# Oasis_embedded_system_2020-12-29_17-35-1.net
KiCad netlist of a schematic drawn in EasyEDA
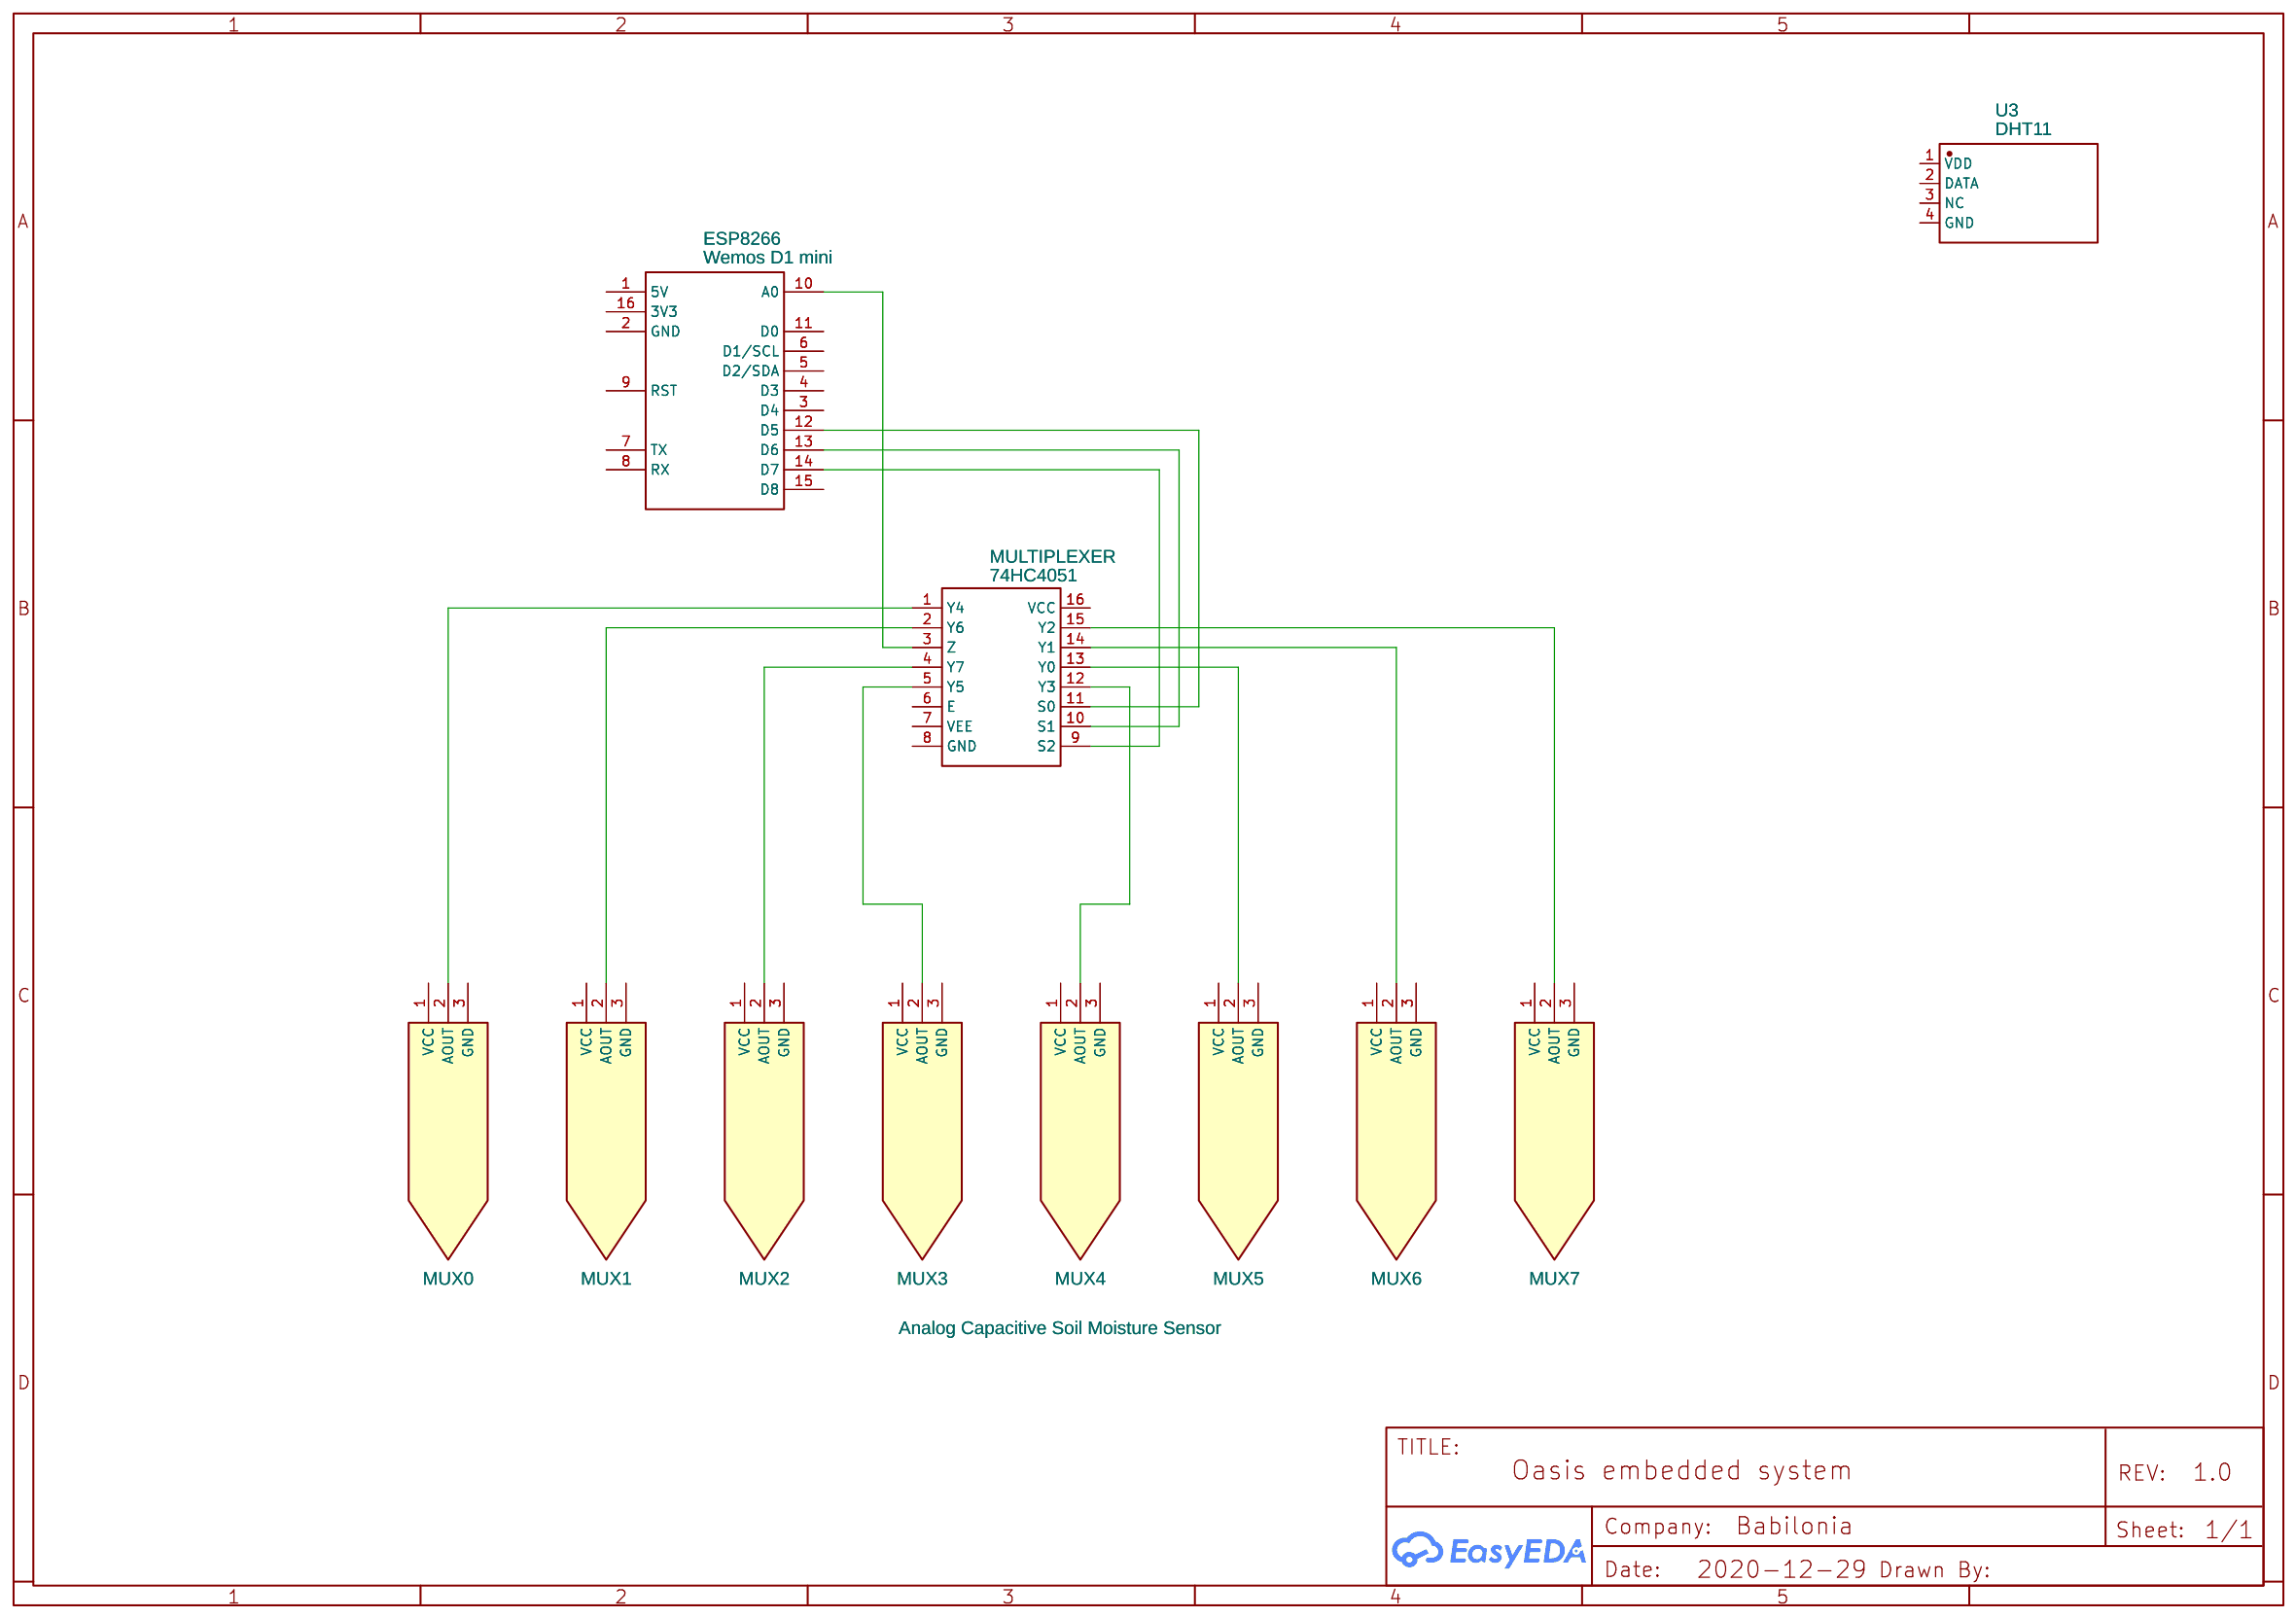
[diagram p0: schematic sheet]

(export (version "E")
  (design (tool "Eeschema 10.0.6"))
  (components
    (comp (ref "ESP8266") (value "Wemos D1 mini") (libsource (lib "") (part "Wemos D1 mini")))
    (comp (ref "MULTIPLEXER") (value "74HC4051") (libsource (lib "") (part "74HC4051")))
    (comp (ref "MUX0")
      (value "Analog Capacitive Soil Moisture Sensor")
      (fields (field (name "BOM_Manufacturer Part") "New SchematicLib"))
      (libsource (lib "") (part "Analog Capacitive Soil Moisture Sensor"))
    )
    (comp (ref "MUX1")
      (value "Analog Capacitive Soil Moisture Sensor")
      (fields (field (name "BOM_Manufacturer Part") "New SchematicLib"))
      (libsource (lib "") (part "Analog Capacitive Soil Moisture Sensor"))
    )
    (comp (ref "MUX2")
      (value "Analog Capacitive Soil Moisture Sensor")
      (fields (field (name "BOM_Manufacturer Part") "New SchematicLib"))
      (libsource (lib "") (part "Analog Capacitive Soil Moisture Sensor"))
    )
    (comp (ref "MUX3")
      (value "Analog Capacitive Soil Moisture Sensor")
      (fields (field (name "BOM_Manufacturer Part") "New SchematicLib"))
      (libsource (lib "") (part "Analog Capacitive Soil Moisture Sensor"))
    )
    (comp (ref "MUX4")
      (value "Analog Capacitive Soil Moisture Sensor")
      (fields (field (name "BOM_Manufacturer Part") "New SchematicLib"))
      (libsource (lib "") (part "Analog Capacitive Soil Moisture Sensor"))
    )
    (comp (ref "MUX5")
      (value "Analog Capacitive Soil Moisture Sensor")
      (fields (field (name "BOM_Manufacturer Part") "New SchematicLib"))
      (libsource (lib "") (part "Analog Capacitive Soil Moisture Sensor"))
    )
    (comp (ref "MUX6")
      (value "Analog Capacitive Soil Moisture Sensor")
      (fields (field (name "BOM_Manufacturer Part") "New SchematicLib"))
      (libsource (lib "") (part "Analog Capacitive Soil Moisture Sensor"))
    )
    (comp (ref "MUX7")
      (value "Analog Capacitive Soil Moisture Sensor")
      (fields (field (name "BOM_Manufacturer Part") "New SchematicLib"))
      (libsource (lib "") (part "Analog Capacitive Soil Moisture Sensor"))
    )
    (comp (ref "U3")
      (value "DHT11")
      (fields (field (name "BOM_Supplier Part") "C117051"))
      (libsource (lib "") (part "DHT11"))
    )
  )
  (nets
    (net (code "1") (name "Net-(ESP8266-A0)") (class "Default")
      (node (ref "ESP8266") (pin "10") (pinfunction "A0_10") (pintype "unspecified"))
      (node (ref "MULTIPLEXER") (pin "3") (pinfunction "Z_3") (pintype "unspecified"))
    )
    (net (code "2") (name "Net-(ESP8266-D5)") (class "Default")
      (node (ref "ESP8266") (pin "12") (pinfunction "D5_12") (pintype "unspecified"))
      (node (ref "MULTIPLEXER") (pin "11") (pinfunction "S0_11") (pintype "input"))
    )
    (net (code "3") (name "Net-(ESP8266-D6)") (class "Default")
      (node (ref "ESP8266") (pin "13") (pinfunction "D6_13") (pintype "unspecified"))
      (node (ref "MULTIPLEXER") (pin "10") (pinfunction "S1_10") (pintype "input"))
    )
    (net (code "4") (name "Net-(ESP8266-D7)") (class "Default")
      (node (ref "ESP8266") (pin "14") (pinfunction "D7_14") (pintype "unspecified"))
      (node (ref "MULTIPLEXER") (pin "9") (pinfunction "S2_9") (pintype "input"))
    )
    (net (code "5") (name "Net-(MULTIPLEXER-Y0)") (class "Default")
      (node (ref "MULTIPLEXER") (pin "13") (pinfunction "Y0_13") (pintype "bidirectional"))
      (node (ref "MUX5") (pin "2") (pinfunction "AOUT_2") (pintype "unspecified"))
    )
    (net (code "6") (name "Net-(MULTIPLEXER-Y1)") (class "Default")
      (node (ref "MULTIPLEXER") (pin "14") (pinfunction "Y1_14") (pintype "bidirectional"))
      (node (ref "MUX6") (pin "2") (pinfunction "AOUT_2") (pintype "unspecified"))
    )
    (net (code "7") (name "Net-(MULTIPLEXER-Y2)") (class "Default")
      (node (ref "MULTIPLEXER") (pin "15") (pinfunction "Y2_15") (pintype "bidirectional"))
      (node (ref "MUX7") (pin "2") (pinfunction "AOUT_2") (pintype "unspecified"))
    )
    (net (code "8") (name "Net-(MULTIPLEXER-Y3)") (class "Default")
      (node (ref "MULTIPLEXER") (pin "12") (pinfunction "Y3_12") (pintype "bidirectional"))
      (node (ref "MUX4") (pin "2") (pinfunction "AOUT_2") (pintype "unspecified"))
    )
    (net (code "9") (name "Net-(MULTIPLEXER-Y4)") (class "Default")
      (node (ref "MULTIPLEXER") (pin "1") (pinfunction "Y4_1") (pintype "bidirectional"))
      (node (ref "MUX0") (pin "2") (pinfunction "AOUT_2") (pintype "unspecified"))
    )
    (net (code "10") (name "Net-(MULTIPLEXER-Y5)") (class "Default")
      (node (ref "MULTIPLEXER") (pin "5") (pinfunction "Y5_5") (pintype "bidirectional"))
      (node (ref "MUX3") (pin "2") (pinfunction "AOUT_2") (pintype "unspecified"))
    )
    (net (code "11") (name "Net-(MULTIPLEXER-Y6)") (class "Default")
      (node (ref "MULTIPLEXER") (pin "2") (pinfunction "Y6_2") (pintype "bidirectional"))
      (node (ref "MUX1") (pin "2") (pinfunction "AOUT_2") (pintype "unspecified"))
    )
    (net (code "12") (name "Net-(MULTIPLEXER-Y7)") (class "Default")
      (node (ref "MULTIPLEXER") (pin "4") (pinfunction "Y7_4") (pintype "bidirectional"))
      (node (ref "MUX2") (pin "2") (pinfunction "AOUT_2") (pintype "unspecified"))
    )
    (net (code "13") (name "unconnected-(ESP8266-3V3-Pad16)") (class "Default")
      (node (ref "ESP8266") (pin "16") (pinfunction "3V3_16") (pintype "unspecified"))
    )
    (net (code "14") (name "unconnected-(ESP8266-5V-Pad1)") (class "Default")
      (node (ref "ESP8266") (pin "1") (pinfunction "5V_1") (pintype "unspecified"))
    )
    (net (code "15") (name "unconnected-(ESP8266-D0-Pad11)") (class "Default")
      (node (ref "ESP8266") (pin "11") (pinfunction "D0_11") (pintype "unspecified"))
    )
    (net (code "16") (name "unconnected-(ESP8266-D1{slash}SCL-Pad6)") (class "Default")
      (node (ref "ESP8266") (pin "6") (pinfunction "D1/SCL_6") (pintype "unspecified"))
    )
    (net (code "17") (name "unconnected-(ESP8266-D2{slash}SDA-Pad5)") (class "Default")
      (node (ref "ESP8266") (pin "5") (pinfunction "D2/SDA_5") (pintype "unspecified"))
    )
    (net (code "18") (name "unconnected-(ESP8266-D3-Pad4)") (class "Default")
      (node (ref "ESP8266") (pin "4") (pinfunction "D3_4") (pintype "unspecified"))
    )
    (net (code "19") (name "unconnected-(ESP8266-D4-Pad3)") (class "Default")
      (node (ref "ESP8266") (pin "3") (pinfunction "D4_3") (pintype "unspecified"))
    )
    (net (code "20") (name "unconnected-(ESP8266-D8-Pad15)") (class "Default")
      (node (ref "ESP8266") (pin "15") (pinfunction "D8_15") (pintype "unspecified"))
    )
    (net (code "21") (name "unconnected-(ESP8266-GND-Pad2)") (class "Default")
      (node (ref "ESP8266") (pin "2") (pinfunction "GND_2") (pintype "unspecified"))
    )
    (net (code "22") (name "unconnected-(ESP8266-RST-Pad9)") (class "Default")
      (node (ref "ESP8266") (pin "9") (pinfunction "RST_9") (pintype "unspecified"))
    )
    (net (code "23") (name "unconnected-(ESP8266-RX-Pad8)") (class "Default")
      (node (ref "ESP8266") (pin "8") (pinfunction "RX_8") (pintype "unspecified"))
    )
    (net (code "24") (name "unconnected-(ESP8266-TX-Pad7)") (class "Default")
      (node (ref "ESP8266") (pin "7") (pinfunction "TX_7") (pintype "unspecified"))
    )
    (net (code "25") (name "unconnected-(MULTIPLEXER-E-Pad6)") (class "Default")
      (node (ref "MULTIPLEXER") (pin "6") (pinfunction "E_6") (pintype "input"))
    )
    (net (code "26") (name "unconnected-(MULTIPLEXER-GND-Pad8)") (class "Default")
      (node (ref "MULTIPLEXER") (pin "8") (pinfunction "GND_8") (pintype "bidirectional"))
    )
    (net (code "27") (name "unconnected-(MULTIPLEXER-VCC-Pad16)") (class "Default")
      (node (ref "MULTIPLEXER") (pin "16") (pinfunction "VCC_16") (pintype "bidirectional"))
    )
    (net (code "28") (name "unconnected-(MULTIPLEXER-VEE-Pad7)") (class "Default")
      (node (ref "MULTIPLEXER") (pin "7") (pinfunction "VEE_7") (pintype "bidirectional"))
    )
    (net (code "29") (name "unconnected-(MUX0-GND-Pad3)") (class "Default")
      (node (ref "MUX0") (pin "3") (pinfunction "GND_3") (pintype "unspecified"))
    )
    (net (code "30") (name "unconnected-(MUX0-VCC-Pad1)") (class "Default")
      (node (ref "MUX0") (pin "1") (pinfunction "VCC_1") (pintype "unspecified"))
    )
    (net (code "31") (name "unconnected-(MUX1-GND-Pad3)") (class "Default")
      (node (ref "MUX1") (pin "3") (pinfunction "GND_3") (pintype "unspecified"))
    )
    (net (code "32") (name "unconnected-(MUX1-VCC-Pad1)") (class "Default")
      (node (ref "MUX1") (pin "1") (pinfunction "VCC_1") (pintype "unspecified"))
    )
    (net (code "33") (name "unconnected-(MUX2-GND-Pad3)") (class "Default")
      (node (ref "MUX2") (pin "3") (pinfunction "GND_3") (pintype "unspecified"))
    )
    (net (code "34") (name "unconnected-(MUX2-VCC-Pad1)") (class "Default")
      (node (ref "MUX2") (pin "1") (pinfunction "VCC_1") (pintype "unspecified"))
    )
    (net (code "35") (name "unconnected-(MUX3-GND-Pad3)") (class "Default")
      (node (ref "MUX3") (pin "3") (pinfunction "GND_3") (pintype "unspecified"))
    )
    (net (code "36") (name "unconnected-(MUX3-VCC-Pad1)") (class "Default")
      (node (ref "MUX3") (pin "1") (pinfunction "VCC_1") (pintype "unspecified"))
    )
    (net (code "37") (name "unconnected-(MUX4-GND-Pad3)") (class "Default")
      (node (ref "MUX4") (pin "3") (pinfunction "GND_3") (pintype "unspecified"))
    )
    (net (code "38") (name "unconnected-(MUX4-VCC-Pad1)") (class "Default")
      (node (ref "MUX4") (pin "1") (pinfunction "VCC_1") (pintype "unspecified"))
    )
    (net (code "39") (name "unconnected-(MUX5-GND-Pad3)") (class "Default")
      (node (ref "MUX5") (pin "3") (pinfunction "GND_3") (pintype "unspecified"))
    )
    (net (code "40") (name "unconnected-(MUX5-VCC-Pad1)") (class "Default")
      (node (ref "MUX5") (pin "1") (pinfunction "VCC_1") (pintype "unspecified"))
    )
    (net (code "41") (name "unconnected-(MUX6-GND-Pad3)") (class "Default")
      (node (ref "MUX6") (pin "3") (pinfunction "GND_3") (pintype "unspecified"))
    )
    (net (code "42") (name "unconnected-(MUX6-VCC-Pad1)") (class "Default")
      (node (ref "MUX6") (pin "1") (pinfunction "VCC_1") (pintype "unspecified"))
    )
    (net (code "43") (name "unconnected-(MUX7-GND-Pad3)") (class "Default")
      (node (ref "MUX7") (pin "3") (pinfunction "GND_3") (pintype "unspecified"))
    )
    (net (code "44") (name "unconnected-(MUX7-VCC-Pad1)") (class "Default")
      (node (ref "MUX7") (pin "1") (pinfunction "VCC_1") (pintype "unspecified"))
    )
    (net (code "45") (name "unconnected-(U3-DATA-Pad2)") (class "Default")
      (node (ref "U3") (pin "2") (pinfunction "DATA_2") (pintype "unspecified"))
    )
    (net (code "46") (name "unconnected-(U3-GND-Pad4)") (class "Default")
      (node (ref "U3") (pin "4") (pinfunction "GND_4") (pintype "unspecified"))
    )
    (net (code "47") (name "unconnected-(U3-NC-Pad3)") (class "Default")
      (node (ref "U3") (pin "3") (pinfunction "NC_3") (pintype "unspecified"))
    )
    (net (code "48") (name "unconnected-(U3-VDD-Pad1)") (class "Default")
      (node (ref "U3") (pin "1") (pinfunction "VDD_1") (pintype "unspecified"))
    )
  )
)
